# charger.net
KiCad netlist of a schematic drawn in Altium Designer
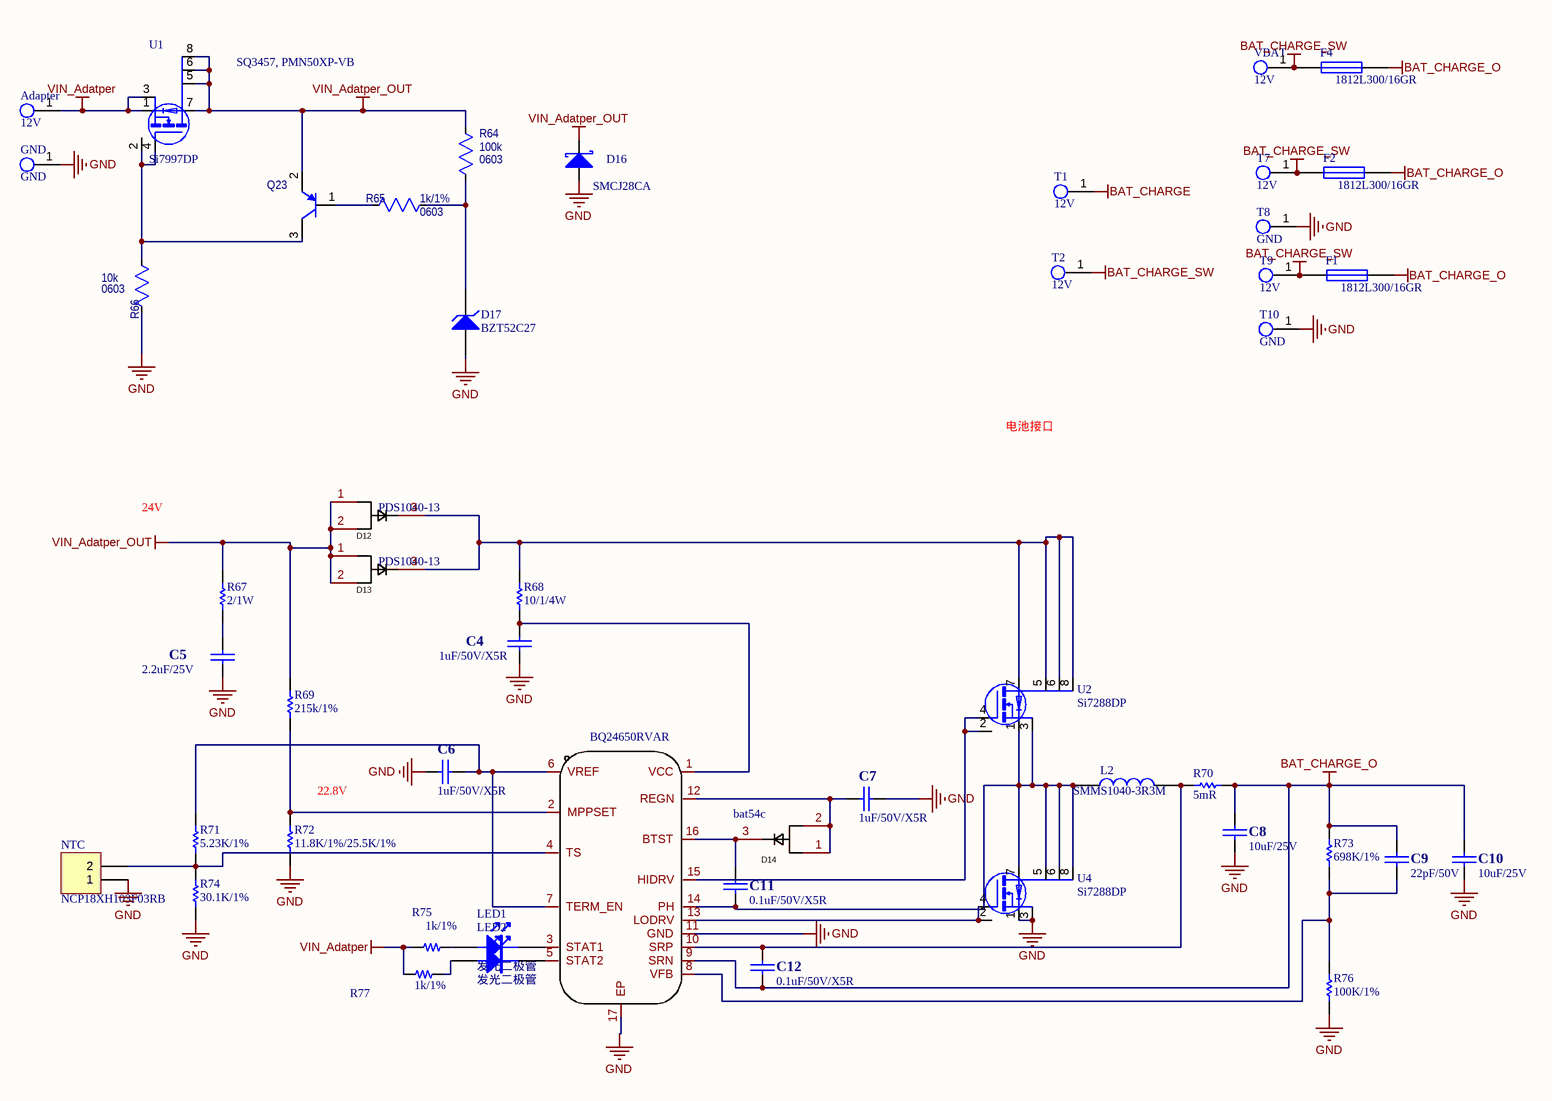
[diagram p0: charger.SchDoc]

(export (version "E")
  (design (tool "Eeschema 10.0.6"))
  (components
    (comp (ref "Adapter") (value "12V") (footprint "FIX-4.5") (libsource (lib "Schlib_20110825") (part "TP")))
    (comp (ref "C4")
      (value "1uF/50V/X5R")
      (footprint "0805C")
      (description "Capacitor")
      (libsource (lib "*") (part "CAP"))
    )
    (comp (ref "C5")
      (value "2.2uF/25V")
      (footprint "1210C")
      (description "Capacitor")
      (libsource (lib "*") (part "CAP"))
    )
    (comp (ref "C6")
      (value "1uF/50V/X5R")
      (footprint "0603C")
      (description "Capacitor")
      (libsource (lib "*") (part "CAP"))
    )
    (comp (ref "C7")
      (value "1uF/50V/X5R")
      (footprint "0603C")
      (description "Capacitor")
      (libsource (lib "*") (part "CAP"))
    )
    (comp (ref "C8")
      (value "10uF/25V")
      (footprint "0603C")
      (description "Capacitor")
      (libsource (lib "*") (part "CAP"))
    )
    (comp (ref "C9")
      (value "22pF/50V")
      (footprint "0603C")
      (description "Capacitor")
      (libsource (lib "*") (part "CAP"))
    )
    (comp (ref "C10")
      (value "10uF/25V")
      (footprint "0603C")
      (description "Capacitor")
      (libsource (lib "*") (part "CAP"))
    )
    (comp (ref "C11")
      (value "0.1uF/50V/X5R")
      (footprint "0603C")
      (description "Capacitor")
      (libsource (lib "*") (part "CAP"))
    )
    (comp (ref "C12")
      (value "0.1uF/50V/X5R")
      (footprint "0603C")
      (description "Capacitor")
      (libsource (lib "*") (part "CAP"))
    )
    (comp (ref "D12")
      (value "PDS1040-13")
      (footprint "POWERDI-5_L5.4-W4.0-LS6.5-RD")
      (fields (field (name "MANUFACTURER") "DIODES(美台)"))
      (libsource (lib "Schlib_20110825") (part "PDS1040-13"))
    )
    (comp (ref "D13")
      (value "PDS1040-13")
      (footprint "POWERDI-5_L5.4-W4.0-LS6.5-RD")
      (fields (field (name "MANUFACTURER") "DIODES(美台)"))
      (libsource (lib "Schlib_20110825") (part "PDS1040-13"))
    )
    (comp (ref "D14")
      (value "bat54c")
      (footprint "sot23-3")
      (fields (field (name "MANUFACTURER") "DIODES(美台)") (field (name "MANUFACTURER PART") "PDS1040-13"))
      (libsource (lib "Schlib_20110825") (part "PDS1040-13"))
    )
    (comp (ref "D16")
      (value "SMCJ28CA")
      (footprint "SMC")
      (description "Schottky Diode")
      (libsource (lib "*") (part "DIODE S"))
    )
    (comp (ref "D17")
      (value "BZT52C27")
      (footprint "sod123")
      (libsource (lib "Bogen") (part "BZT52C12S-7-F"))
    )
    (comp (ref "F1")
      (value "1812L300/16GR")
      (footprint "1812-F")
      (description "Fuse")
      (fields (field (name "PUBLISHER") "Altium Limited"))
      (libsource (lib "Miscellaneous Devices") (part "Fuse 1"))
    )
    (comp (ref "F2")
      (value "1812L300/16GR")
      (footprint "1812-F")
      (description "Fuse")
      (fields (field (name "PUBLISHER") "Altium Limited"))
      (libsource (lib "Miscellaneous Devices") (part "Fuse 1"))
    )
    (comp (ref "F4")
      (value "1812L300/16GR")
      (footprint "1812-F")
      (description "Fuse")
      (fields (field (name "PUBLISHER") "Altium Limited"))
      (libsource (lib "Miscellaneous Devices") (part "Fuse 1"))
    )
    (comp (ref "GND") (value "GND") (footprint "FIX-4.5") (libsource (lib "Schlib_20110825") (part "TP")))
    (comp (ref "L2") (value "SMMS1040-3R3M") (footprint "MSS1038") (libsource (lib "*") (part "INDUCTOR")))
    (comp (ref "LED1") (value "发光二极管") (footprint "0603LED") (libsource (lib "*") (part "LED")))
    (comp (ref "LED2") (value "发光二极管") (footprint "0603LED") (libsource (lib "*") (part "LED")))
    (comp (ref "NTC")
      (value "NCP18XH103F03RB")
      (footprint "HDR1X2")
      (description "XH2.54 2P 立贴")
      (fields (field (name "PUBLISHER") "Altium Limited"))
      (libsource (lib "Miscellaneous Connectors") (part "Header 2"))
    )
    (comp (ref "Q23")
      (value "MMBT4403-7-F")
      (footprint "SOT23-3")
      (libsource (lib "Karl") (part "OEM_Diodes_MMBT4403"))
    )
    (comp (ref "R64")
      (value "100k")
      (footprint "0603R")
      (fields
        (field (name "PARTNUMBER") "RC0603FR-0716K9L")
        (field (name "TOLERANCE") "tol")
        (field (name "PACKAGE") "0603")
        (field (name "Comment") "100K/1%")
      )
      (libsource (lib "Karl") (part "Resistor_0603"))
    )
    (comp (ref "R65")
      (value "1k/1%")
      (footprint "0603R")
      (fields
        (field (name "PARTNUMBER") "RC0603FR-071KL")
        (field (name "TOLERANCE") "tol")
        (field (name "PACKAGE") "0603")
      )
      (libsource (lib "Karl") (part "Resistor_0603"))
    )
    (comp (ref "R66")
      (value "10k")
      (footprint "0603R")
      (fields
        (field (name "PARTNUMBER") "RC0603FR-071KL")
        (field (name "TOLERANCE") "tol")
        (field (name "PACKAGE") "0603")
      )
      (libsource (lib "Karl") (part "Resistor_0603"))
    )
    (comp (ref "R67")
      (value "2/1W")
      (footprint "2512R")
      (description "Resistor")
      (fields (field (name "PUBLISHER") "Altium Limited"))
      (libsource (lib "Miscellaneous Devices") (part "Res1"))
    )
    (comp (ref "R68")
      (value "10/1/4W")
      (footprint "1206R")
      (description "Resistor")
      (fields (field (name "PUBLISHER") "Altium Limited"))
      (libsource (lib "Miscellaneous Devices") (part "Res1"))
    )
    (comp (ref "R69")
      (value "215k/1%")
      (footprint "0603R")
      (description "Resistor")
      (fields (field (name "PUBLISHER") "Altium Limited"))
      (libsource (lib "Miscellaneous Devices") (part "Res1"))
    )
    (comp (ref "R70")
      (value "5mR")
      (footprint "2512R")
      (description "Resistor")
      (fields (field (name "PUBLISHER") "Altium Limited"))
      (libsource (lib "Miscellaneous Devices") (part "Res1"))
    )
    (comp (ref "R71")
      (value "5.23K/1%")
      (footprint "0603R")
      (description "Resistor")
      (fields (field (name "PUBLISHER") "Altium Limited"))
      (libsource (lib "Miscellaneous Devices") (part "Res1"))
    )
    (comp (ref "R72")
      (value "11.8K/1%/25.5K/1%")
      (footprint "0603R")
      (description "Resistor")
      (fields (field (name "PUBLISHER") "Altium Limited"))
      (libsource (lib "Miscellaneous Devices") (part "Res1"))
    )
    (comp (ref "R73")
      (value "698K/1%")
      (footprint "0603R")
      (description "Resistor")
      (fields (field (name "PUBLISHER") "Altium Limited"))
      (libsource (lib "Miscellaneous Devices") (part "Res1"))
    )
    (comp (ref "R74")
      (value "30.1K/1%")
      (footprint "0603R")
      (description "Resistor")
      (fields (field (name "PUBLISHER") "Altium Limited"))
      (libsource (lib "Miscellaneous Devices") (part "Res1"))
    )
    (comp (ref "R75") (value "1k/1%") (footprint "0603R") (libsource (lib "JRJ_1") (part "R")))
    (comp (ref "R76")
      (value "100K/1%")
      (footprint "0603R")
      (description "Resistor")
      (fields (field (name "PUBLISHER") "Altium Limited"))
      (libsource (lib "Miscellaneous Devices") (part "Res1"))
    )
    (comp (ref "R77") (value "1k/1%") (footprint "0603R") (libsource (lib "JRJ_1") (part "R")))
    (comp (ref "T1") (value "12V") (footprint "FIX-4.5") (libsource (lib "Schlib_20110825") (part "TP")))
    (comp (ref "T2") (value "12V") (footprint "FIX-4.5") (libsource (lib "Schlib_20110825") (part "TP")))
    (comp (ref "T7") (value "12V") (footprint "FIX-4.5") (libsource (lib "Schlib_20110825") (part "TP")))
    (comp (ref "T8") (value "GND") (footprint "FIX-4.5") (libsource (lib "Schlib_20110825") (part "TP")))
    (comp (ref "T9") (value "12V") (footprint "FIX-4.5") (libsource (lib "Schlib_20110825") (part "TP")))
    (comp (ref "T10") (value "GND") (footprint "FIX-4.5") (libsource (lib "Schlib_20110825") (part "TP")))
    (comp (ref "U1")
      (value "Si7997DP")
      (footprint "PowerPAK SO-8")
      (description "Sia430DJ")
      (libsource (lib "Schlib_20110825") (part "Si7997DP"))
    )
    (comp (ref "U2")
      (value "Si7288DP")
      (footprint "PowerPAK SO-8")
      (description "Sia430DJ")
      (libsource (lib "Schlib_20110825") (part "Si7997DP"))
    )
    (comp (ref "U4")
      (value "Si7288DP")
      (footprint "PowerPAK SO-8")
      (description "Sia430DJ")
      (libsource (lib "Schlib_20110825") (part "Si7997DP"))
    )
    (comp (ref "U5")
      (value "BQ24650RVAR")
      (footprint "VQFN-16_L3.6-W3.6-P0.50-BL-EP")
      (fields (field (name "MANUFACTURER") "TI(德州仪器)"))
      (libsource (lib "Schlib_20110825") (part "BQ24650RVAR"))
    )
    (comp (ref "VBAT") (value "12V") (footprint "FIX-4.5") (libsource (lib "Schlib_20110825") (part "TP")))
  )
  (nets
    (net (code "1") (name "BAT_CHARGE") (class "Default") (node (ref "T1") (pin "1") (pintype "passive")))
    (net (code "2") (name "BAT_CHARGE_O") (class "Default")
      (node (ref "C10") (pin "2") (pinfunction "2_2") (pintype "passive"))
      (node (ref "C12") (pin "1") (pinfunction "1_1") (pintype "passive"))
      (node (ref "C8") (pin "2") (pinfunction "2_2") (pintype "passive"))
      (node (ref "C9") (pin "2") (pinfunction "2_2") (pintype "passive"))
      (node (ref "F1") (pin "2") (pinfunction "2_2") (pintype "passive"))
      (node (ref "F2") (pin "2") (pinfunction "2_2") (pintype "passive"))
      (node (ref "F4") (pin "2") (pinfunction "2_2") (pintype "passive"))
      (node (ref "R70") (pin "2") (pinfunction "2_2") (pintype "passive"))
      (node (ref "R73") (pin "1") (pinfunction "1_1") (pintype "passive"))
      (node (ref "U5") (pin "9") (pinfunction "SRN_9") (pintype "passive"))
    )
    (net (code "3") (name "BAT_CHARGE_SW") (class "Default")
      (node (ref "F1") (pin "1") (pinfunction "1_1") (pintype "passive"))
      (node (ref "F2") (pin "1") (pinfunction "1_1") (pintype "passive"))
      (node (ref "F4") (pin "1") (pinfunction "1_1") (pintype "passive"))
      (node (ref "T2") (pin "1") (pintype "passive"))
      (node (ref "T7") (pin "1") (pintype "passive"))
      (node (ref "T9") (pin "1") (pintype "passive"))
      (node (ref "VBAT") (pin "1") (pintype "passive"))
    )
    (net (code "4") (name "GND") (class "Default")
      (node (ref "C10") (pin "1") (pinfunction "1_1") (pintype "passive"))
      (node (ref "C4") (pin "2") (pinfunction "2_2") (pintype "passive"))
      (node (ref "C5") (pin "2") (pinfunction "2_2") (pintype "passive"))
      (node (ref "C6") (pin "1") (pinfunction "1_1") (pintype "passive"))
      (node (ref "C7") (pin "2") (pinfunction "2_2") (pintype "passive"))
      (node (ref "C8") (pin "1") (pinfunction "1_1") (pintype "passive"))
      (node (ref "D16") (pin "1") (pinfunction "A_1") (pintype "passive"))
      (node (ref "D17") (pin "1") (pinfunction "A_1") (pintype "passive"))
      (node (ref "GND") (pin "1") (pintype "passive"))
      (node (ref "NTC") (pin "1") (pinfunction "1_1") (pintype "passive"))
      (node (ref "R66") (pin "2") (pinfunction "2_2") (pintype "passive"))
      (node (ref "R72") (pin "2") (pinfunction "2_2") (pintype "passive"))
      (node (ref "R74") (pin "2") (pinfunction "2_2") (pintype "passive"))
      (node (ref "R76") (pin "2") (pinfunction "2_2") (pintype "passive"))
      (node (ref "T10") (pin "1") (pintype "passive"))
      (node (ref "T8") (pin "1") (pintype "passive"))
      (node (ref "U4") (pin "1") (pinfunction "S_1") (pintype "passive"))
      (node (ref "U4") (pin "3") (pinfunction "S_3") (pintype "passive"))
      (node (ref "U5") (pin "11") (pinfunction "GND_11") (pintype "passive"))
      (node (ref "U5") (pin "17") (pinfunction "EP_17") (pintype "passive"))
    )
    (net (code "5") (name "Net-(C5-Pad1)") (class "Default")
      (node (ref "C5") (pin "1") (pinfunction "1_1") (pintype "passive"))
      (node (ref "R67") (pin "2") (pinfunction "2_2") (pintype "passive"))
    )
    (net (code "6") (name "Net-(D12-Pad3)") (class "Default")
      (node (ref "D12") (pin "3") (pinfunction "3_3") (pintype "passive"))
      (node (ref "D13") (pin "3") (pinfunction "3_3") (pintype "passive"))
      (node (ref "R68") (pin "1") (pinfunction "1_1") (pintype "passive"))
      (node (ref "U2") (pin "5") (pinfunction "D_5") (pintype "passive"))
      (node (ref "U2") (pin "6") (pinfunction "D_6") (pintype "passive"))
      (node (ref "U2") (pin "7") (pinfunction "D_7") (pintype "passive"))
      (node (ref "U2") (pin "8") (pinfunction "D_8") (pintype "passive"))
    )
    (net (code "7") (name "Net-(D14-LEFT)") (class "Default")
      (node (ref "C7") (pin "1") (pinfunction "1_1") (pintype "passive"))
      (node (ref "D14") (pin "1") (pinfunction "LEFT_1") (pintype "passive"))
      (node (ref "D14") (pin "2") (pinfunction "RIGHT_2") (pintype "passive"))
      (node (ref "U5") (pin "12") (pinfunction "REGN_12") (pintype "passive"))
    )
    (net (code "8") (name "Net-(D17-K)") (class "Default")
      (node (ref "D17") (pin "2") (pinfunction "K_2") (pintype "passive"))
      (node (ref "R64") (pin "1") (pinfunction "1_1") (pintype "passive"))
      (node (ref "R65") (pin "1") (pinfunction "1_1") (pintype "passive"))
    )
    (net (code "9") (name "Net-(LED1-Pad1)") (class "Default")
      (node (ref "LED1") (pin "1") (pinfunction "1_1") (pintype "passive"))
      (node (ref "R75") (pin "1") (pintype "passive"))
    )
    (net (code "10") (name "Net-(LED2-Pad1)") (class "Default")
      (node (ref "LED2") (pin "1") (pinfunction "1_1") (pintype "passive"))
      (node (ref "R77") (pin "1") (pintype "passive"))
    )
    (net (code "11") (name "Net-(Q23-B)") (class "Default")
      (node (ref "Q23") (pin "1") (pinfunction "B_1") (pintype "passive"))
      (node (ref "R65") (pin "2") (pinfunction "2_2") (pintype "passive"))
    )
    (net (code "12") (name "Net-(Q23-C)") (class "Default")
      (node (ref "Q23") (pin "3") (pinfunction "C_3") (pintype "passive"))
      (node (ref "R66") (pin "1") (pinfunction "1_1") (pintype "passive"))
      (node (ref "U1") (pin "2") (pinfunction "G_2") (pintype "passive"))
      (node (ref "U1") (pin "4") (pinfunction "G_4") (pintype "passive"))
    )
    (net (code "13") (name "Net-(U5-BTST)") (class "Default")
      (node (ref "C11") (pin "2") (pinfunction "2_2") (pintype "passive"))
      (node (ref "D14") (pin "3") (pinfunction "3_3") (pintype "passive"))
      (node (ref "U5") (pin "16") (pinfunction "BTST_16") (pintype "passive"))
    )
    (net (code "14") (name "Net-(U5-HIDRV)") (class "Default")
      (node (ref "U2") (pin "2") (pinfunction "G_2") (pintype "passive"))
      (node (ref "U2") (pin "4") (pinfunction "G_4") (pintype "passive"))
      (node (ref "U5") (pin "15") (pinfunction "HIDRV_15") (pintype "passive"))
    )
    (net (code "15") (name "Net-(U5-LODRV)") (class "Default")
      (node (ref "U4") (pin "2") (pinfunction "G_2") (pintype "passive"))
      (node (ref "U4") (pin "4") (pinfunction "G_4") (pintype "passive"))
      (node (ref "U5") (pin "13") (pinfunction "LODRV_13") (pintype "passive"))
    )
    (net (code "16") (name "Net-(U5-MPPSET)") (class "Default")
      (node (ref "R69") (pin "2") (pinfunction "2_2") (pintype "passive"))
      (node (ref "R72") (pin "1") (pinfunction "1_1") (pintype "passive"))
      (node (ref "U5") (pin "2") (pinfunction "MPPSET_2") (pintype "passive"))
    )
    (net (code "17") (name "Net-(U5-PH)") (class "Default")
      (node (ref "C11") (pin "1") (pinfunction "1_1") (pintype "passive"))
      (node (ref "L2") (pin "1") (pinfunction "1_1") (pintype "passive"))
      (node (ref "U2") (pin "1") (pinfunction "S_1") (pintype "passive"))
      (node (ref "U2") (pin "3") (pinfunction "S_3") (pintype "passive"))
      (node (ref "U4") (pin "5") (pinfunction "D_5") (pintype "passive"))
      (node (ref "U4") (pin "6") (pinfunction "D_6") (pintype "passive"))
      (node (ref "U4") (pin "7") (pinfunction "D_7") (pintype "passive"))
      (node (ref "U4") (pin "8") (pinfunction "D_8") (pintype "passive"))
      (node (ref "U5") (pin "14") (pinfunction "PH_14") (pintype "passive"))
    )
    (net (code "18") (name "Net-(U5-SRP)") (class "Default")
      (node (ref "C12") (pin "2") (pinfunction "2_2") (pintype "passive"))
      (node (ref "L2") (pin "2") (pinfunction "2_2") (pintype "passive"))
      (node (ref "R70") (pin "1") (pinfunction "1_1") (pintype "passive"))
      (node (ref "U5") (pin "10") (pinfunction "SRP_10") (pintype "passive"))
    )
    (net (code "19") (name "Net-(U5-STAT1)") (class "Default")
      (node (ref "LED1") (pin "2") (pinfunction "2_2") (pintype "passive"))
      (node (ref "U5") (pin "3") (pinfunction "STAT1_3") (pintype "passive"))
    )
    (net (code "20") (name "Net-(U5-STAT2)") (class "Default")
      (node (ref "LED2") (pin "2") (pinfunction "2_2") (pintype "passive"))
      (node (ref "U5") (pin "5") (pinfunction "STAT2_5") (pintype "passive"))
    )
    (net (code "21") (name "Net-(U5-TERM_EN)") (class "Default")
      (node (ref "C6") (pin "2") (pinfunction "2_2") (pintype "passive"))
      (node (ref "R71") (pin "1") (pinfunction "1_1") (pintype "passive"))
      (node (ref "U5") (pin "6") (pinfunction "VREF_6") (pintype "passive"))
      (node (ref "U5") (pin "7") (pinfunction "TERM_EN_7") (pintype "passive"))
    )
    (net (code "22") (name "Net-(U5-TS)") (class "Default")
      (node (ref "NTC") (pin "2") (pinfunction "2_2") (pintype "passive"))
      (node (ref "R71") (pin "2") (pinfunction "2_2") (pintype "passive"))
      (node (ref "R74") (pin "1") (pinfunction "1_1") (pintype "passive"))
      (node (ref "U5") (pin "4") (pinfunction "TS_4") (pintype "passive"))
    )
    (net (code "23") (name "Net-(U5-VCC)") (class "Default")
      (node (ref "C4") (pin "1") (pinfunction "1_1") (pintype "passive"))
      (node (ref "R68") (pin "2") (pinfunction "2_2") (pintype "passive"))
      (node (ref "U5") (pin "1") (pinfunction "VCC_1") (pintype "passive"))
    )
    (net (code "24") (name "Net-(U5-VFB)") (class "Default")
      (node (ref "C9") (pin "1") (pinfunction "1_1") (pintype "passive"))
      (node (ref "R73") (pin "2") (pinfunction "2_2") (pintype "passive"))
      (node (ref "R76") (pin "1") (pinfunction "1_1") (pintype "passive"))
      (node (ref "U5") (pin "8") (pinfunction "VFB_8") (pintype "passive"))
    )
    (net (code "25") (name "VIN_Adatper") (class "Default")
      (node (ref "Adapter") (pin "1") (pintype "passive"))
      (node (ref "R75") (pin "2") (pintype "passive"))
      (node (ref "R77") (pin "2") (pintype "passive"))
      (node (ref "U1") (pin "1") (pinfunction "S_1") (pintype "passive"))
      (node (ref "U1") (pin "3") (pinfunction "S_3") (pintype "passive"))
    )
    (net (code "26") (name "VIN_Adatper_OUT") (class "Default")
      (node (ref "D12") (pin "1") (pinfunction "LEFT_1") (pintype "passive"))
      (node (ref "D12") (pin "2") (pinfunction "RIGHT_2") (pintype "passive"))
      (node (ref "D13") (pin "1") (pinfunction "LEFT_1") (pintype "passive"))
      (node (ref "D13") (pin "2") (pinfunction "RIGHT_2") (pintype "passive"))
      (node (ref "D16") (pin "2") (pinfunction "K_2") (pintype "passive"))
      (node (ref "Q23") (pin "2") (pinfunction "E_2") (pintype "passive"))
      (node (ref "R64") (pin "2") (pinfunction "2_2") (pintype "passive"))
      (node (ref "R67") (pin "1") (pinfunction "1_1") (pintype "passive"))
      (node (ref "R69") (pin "1") (pinfunction "1_1") (pintype "passive"))
      (node (ref "U1") (pin "5") (pinfunction "D_5") (pintype "passive"))
      (node (ref "U1") (pin "6") (pinfunction "D_6") (pintype "passive"))
      (node (ref "U1") (pin "7") (pinfunction "D_7") (pintype "passive"))
      (node (ref "U1") (pin "8") (pinfunction "D_8") (pintype "passive"))
    )
  )
)
